# rso.net
KiCad netlist of a schematic drawn in EAGLE
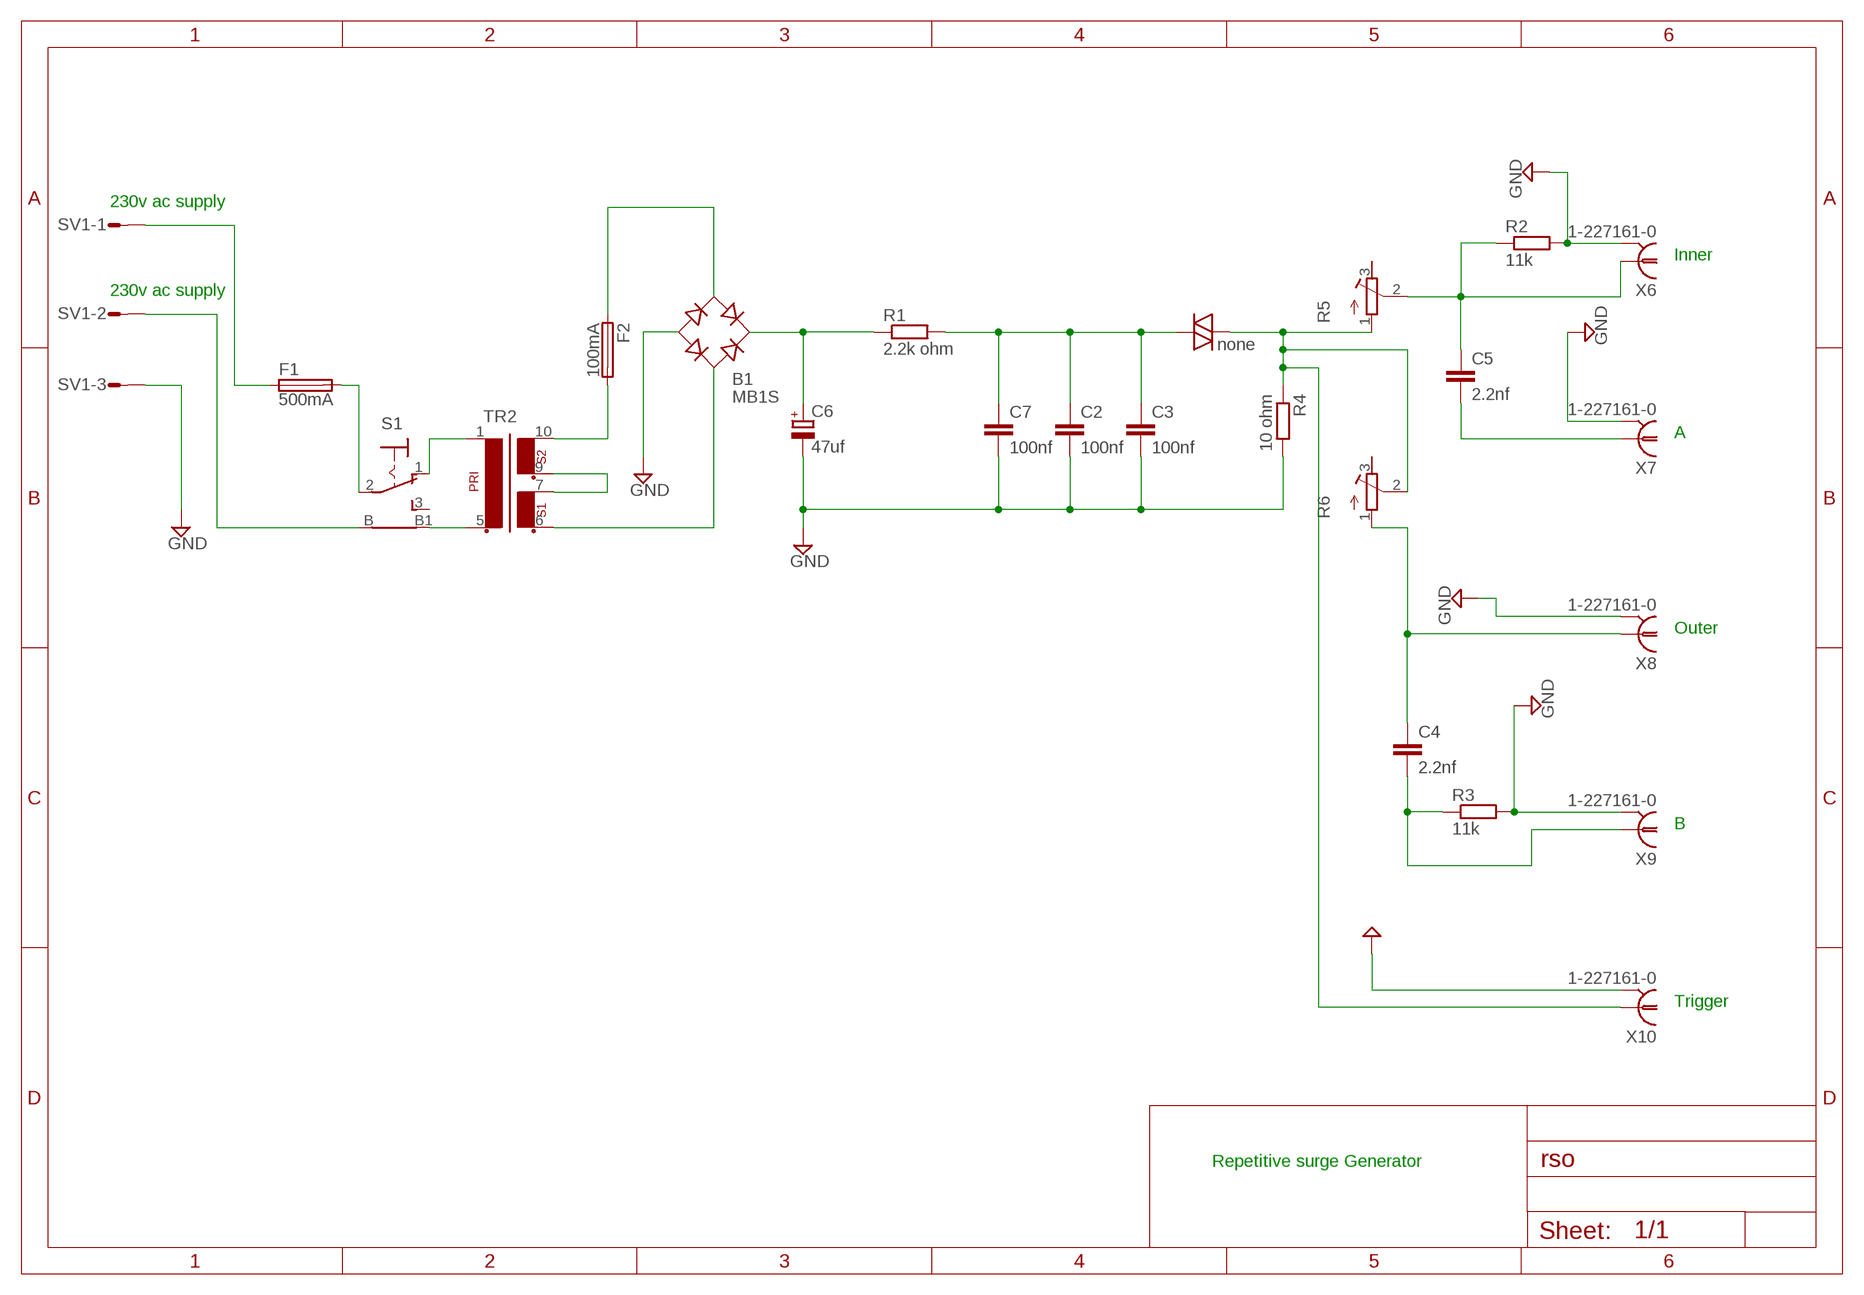
[diagram p0: schematic, sheet 1]

(export (version "E")
  (design (tool "Eeschema 10.0.6"))
  (components
    (comp (ref "B1")
      (value "MB1S")
      (footprint "eagle-import:SOIC-4")
      (fields (field (name "MF") "MULTICOMP"))
      (libsource (lib "eagle-import") (part "MBS1"))
    )
    (comp (ref "C2")
      (value "100nf")
      (footprint "eagle-import:C0805")
      (fields (field (name "MF") "AVX") (field (name "MPN") "08055C104KAZ2A"))
      (libsource (lib "eagle-import") (part "C-EUC0805"))
    )
    (comp (ref "C3")
      (value "100nf")
      (footprint "eagle-import:C0805")
      (fields (field (name "MF") "AVX") (field (name "MPN") "08055C104KAZ2A"))
      (libsource (lib "eagle-import") (part "C-EUC0805"))
    )
    (comp (ref "C4")
      (value "2.2nf")
      (footprint "eagle-import:C0805")
      (fields (field (name "MF") "AVX") (field (name "MPN") "04025C222JAT2A"))
      (libsource (lib "eagle-import") (part "C-EUC0805"))
    )
    (comp (ref "C5")
      (value "2.2nf")
      (footprint "eagle-import:C0805")
      (fields (field (name "MF") "AVX") (field (name "MPN") "04025C222JAT2A"))
      (libsource (lib "eagle-import") (part "C-EUC0805"))
    )
    (comp (ref "C6")
      (value "47uf")
      (footprint "eagle-import:140CLH-1010")
      (fields (field (name "MF") "PANASONIC") (field (name "MPN") "EEEFK1K470P"))
      (libsource (lib "eagle-import") (part "CPOL-EU140CLH-1010"))
    )
    (comp (ref "C7")
      (value "100nf")
      (footprint "eagle-import:C0805")
      (fields (field (name "MF") "AVX") (field (name "MPN") "08055C104KAZ2A"))
      (libsource (lib "eagle-import") (part "C-EUC0805"))
    )
    (comp (ref "D1")
      (value "none")
      (footprint "eagle-import:DO35-10")
      (fields (field (name "MF") "NTE ELECTRONICS") (field (name "MPN") "NTE6408"))
      (libsource (lib "eagle-import") (part "DIAC-DO35-10"))
    )
    (comp (ref "F1")
      (value "500mA")
      (footprint "eagle-import:SH22,5A")
      (fields
        (field (name "MPN") "0031.7701.11")
        (field (name "MF") "ARCOLECTRIC")
        (field (name "MPN_1") "C0345RAAAA")
        (field (name "OC_FARNELL") "149862")
      )
      (libsource (lib "eagle-import") (part "SH22,5A"))
    )
    (comp (ref "F2")
      (value "100mA")
      (footprint "eagle-import:SH22,5A")
      (fields
        (field (name "MPN") "0031.7701.11")
        (field (name "MF") "ARCOLECTRIC")
        (field (name "MPN_1") "C0345RAAAA")
        (field (name "OC_FARNELL") "149862")
      )
      (libsource (lib "eagle-import") (part "SH22,5A"))
    )
    (comp (ref "R1")
      (value "2.2k ohm")
      (footprint "eagle-import:R2512W")
      (fields (field (name "MF") "VISHAY") (field (name "MPN") "CRCW08052K20FKEA"))
      (libsource (lib "eagle-import") (part "R-EU_R2512W"))
    )
    (comp (ref "R2")
      (value "11k")
      (footprint "eagle-import:M0805")
      (fields (field (name "MF") "MULTICOMP") (field (name "MPN") "MCMR08X1102FTL"))
      (libsource (lib "eagle-import") (part "R-EU_M0805"))
    )
    (comp (ref "R3")
      (value "11k")
      (footprint "eagle-import:M0805")
      (fields (field (name "MF") "MULTICOMP") (field (name "MPN") "MCMR08X1102FTL"))
      (libsource (lib "eagle-import") (part "R-EU_M0805"))
    )
    (comp (ref "R4")
      (value "10 ohm")
      (footprint "eagle-import:M0805")
      (fields (field (name "MF") "BOURNS") (field (name "MPN") "CRT1206-BY-10R0ELF"))
      (libsource (lib "eagle-import") (part "R-EU_M0805"))
    )
    (comp (ref "R5")
      (value "R-TRIMM3339P")
      (footprint "eagle-import:RTRIM3339P")
      (fields (field (name "MF") "VISHAY") (field (name "MPN") "534B1101JL"))
      (libsource (lib "eagle-import") (part "R-TRIMM3339P"))
    )
    (comp (ref "R6")
      (value "R-TRIMM3339P")
      (footprint "eagle-import:RTRIM3339P")
      (fields (field (name "MF") "VISHAY") (field (name "MPN") "534B1101JL"))
      (libsource (lib "eagle-import") (part "R-TRIMM3339P"))
    )
    (comp (ref "S1")
      (value "LPV-1")
      (footprint "eagle-import:LPV-1")
      (fields (field (name "MF") "QUALTEK ELECTRONICS") (field (name "MPN") "761-18/003"))
      (libsource (lib "eagle-import") (part "LPV-1"))
    )
    (comp (ref "SV1")
      (value "L03P")
      (footprint "eagle-import:L03P")
      (fields
        (field (name "MF") "JST (JAPAN SOLDERLESS TERMINALS)")
        (field (name "MPN") "B03B-XASK-1(LF)(SN)")
        (field (name "OC_FARNELL") "9492070")
      )
      (libsource (lib "eagle-import") (part "L03P"))
    )
    (comp (ref "TR2")
      (value "EI38-2")
      (footprint "eagle-import:EI38-2")
      (fields (field (name "MF") "MYRRA") (field (name "MPN") "44203"))
      (libsource (lib "eagle-import") (part "EI38-2"))
    )
    (comp (ref "X6")
      (value "1-227161-0")
      (footprint "eagle-import:AMP_227161")
      (fields
        (field (name "MF") "TYCO ELECTRONICS")
        (field (name "MPN") "1-227161")
        (field (name "MF_1") "GREENPAR - TE CONNECTIVITY")
        (field (name "MPN_1") "1-1337542-0")
        (field (name "OC_FARNELL") "1020954")
      )
      (libsource (lib "eagle-import") (part "?2271611--0"))
    )
    (comp (ref "X7")
      (value "1-227161-0")
      (footprint "eagle-import:AMP_227161")
      (fields
        (field (name "MF") "TYCO ELECTRONICS")
        (field (name "MPN") "1-227161")
        (field (name "MF_1") "GREENPAR - TE CONNECTIVITY")
        (field (name "MPN_1") "1-1337542-0")
        (field (name "OC_FARNELL") "1020954")
      )
      (libsource (lib "eagle-import") (part "?2271611--0"))
    )
    (comp (ref "X8")
      (value "1-227161-0")
      (footprint "eagle-import:AMP_227161")
      (fields
        (field (name "MF") "TYCO ELECTRONICS")
        (field (name "MPN") "1-227161")
        (field (name "MF_1") "GREENPAR - TE CONNECTIVITY")
        (field (name "MPN_1") "1-1337542-0")
        (field (name "OC_FARNELL") "1020954")
      )
      (libsource (lib "eagle-import") (part "?2271611--0"))
    )
    (comp (ref "X9")
      (value "1-227161-0")
      (footprint "eagle-import:AMP_227161")
      (fields
        (field (name "MF") "TYCO ELECTRONICS")
        (field (name "MPN") "1-227161")
        (field (name "MF_1") "GREENPAR - TE CONNECTIVITY")
        (field (name "MPN_1") "1-1337542-0")
        (field (name "OC_FARNELL") "1020954")
      )
      (libsource (lib "eagle-import") (part "?2271611--0"))
    )
    (comp (ref "X10")
      (value "1-227161-0")
      (footprint "eagle-import:AMP_227161")
      (fields
        (field (name "MF") "TYCO ELECTRONICS")
        (field (name "MPN") "1-227161")
        (field (name "MF_1") "GREENPAR - TE CONNECTIVITY")
        (field (name "MPN_1") "1-1337542-0")
        (field (name "OC_FARNELL") "1020954")
      )
      (libsource (lib "eagle-import") (part "?2271611--0"))
    )
  )
  (nets
    (net (code "1") (name "GND") (class "Default")
      (node (ref "B1") (pin "-") (pinfunction "-_-") (pintype "passive"))
      (node (ref "C2") (pin "2") (pinfunction "2_2") (pintype "passive"))
      (node (ref "C3") (pin "2") (pinfunction "2_2") (pintype "passive"))
      (node (ref "C6") (pin "-") (pinfunction "-_-") (pintype "passive"))
      (node (ref "C7") (pin "2") (pinfunction "2_2") (pintype "passive"))
      (node (ref "R2") (pin "2") (pinfunction "2_2") (pintype "passive"))
      (node (ref "R3") (pin "2") (pinfunction "2_2") (pintype "passive"))
      (node (ref "R4") (pin "2") (pinfunction "2_2") (pintype "passive"))
      (node (ref "SV1") (pin "3") (pinfunction "S_3") (pintype "passive"))
      (node (ref "X10") (pin "2") (pinfunction "2_2") (pintype "passive"))
      (node (ref "X6") (pin "2") (pinfunction "2_2") (pintype "passive"))
      (node (ref "X7") (pin "2") (pinfunction "2_2") (pintype "passive"))
      (node (ref "X8") (pin "2") (pinfunction "2_2") (pintype "passive"))
      (node (ref "X9") (pin "2") (pinfunction "2_2") (pintype "passive"))
    )
    (net (code "2") (name "Net-(B1-AC1)") (class "Default")
      (node (ref "B1") (pin "~1") (pinfunction "AC1_~1") (pintype "passive"))
      (node (ref "F2") (pin "1") (pinfunction "1_1") (pintype "passive"))
    )
    (net (code "3") (name "Net-(B1-AC2)") (class "Default")
      (node (ref "B1") (pin "~2") (pinfunction "AC2_~2") (pintype "passive"))
      (node (ref "TR2") (pin "6") (pinfunction "3_6") (pintype "passive"))
    )
    (net (code "4") (name "Net-(B1-Pad+)") (class "Default")
      (node (ref "B1") (pin "+") (pinfunction "+_+") (pintype "passive"))
      (node (ref "C6") (pin "+") (pinfunction "+_+") (pintype "passive"))
      (node (ref "R1") (pin "1") (pinfunction "1_1") (pintype "passive"))
    )
    (net (code "5") (name "Net-(C4-Pad2)") (class "Default")
      (node (ref "C4") (pin "2") (pinfunction "2_2") (pintype "passive"))
      (node (ref "R3") (pin "1") (pinfunction "1_1") (pintype "passive"))
      (node (ref "X9") (pin "1") (pinfunction "1_1") (pintype "passive"))
    )
    (net (code "6") (name "Net-(C5-Pad2)") (class "Default")
      (node (ref "C5") (pin "2") (pinfunction "2_2") (pintype "passive"))
      (node (ref "X7") (pin "1") (pinfunction "1_1") (pintype "passive"))
    )
    (net (code "7") (name "Net-(D1-1)") (class "Default")
      (node (ref "C2") (pin "1") (pinfunction "1_1") (pintype "passive"))
      (node (ref "C3") (pin "1") (pinfunction "1_1") (pintype "passive"))
      (node (ref "C7") (pin "1") (pinfunction "1_1") (pintype "passive"))
      (node (ref "D1") (pin "A") (pinfunction "1_A") (pintype "passive"))
      (node (ref "R1") (pin "2") (pinfunction "2_2") (pintype "passive"))
    )
    (net (code "8") (name "Net-(D1-2)") (class "Default")
      (node (ref "D1") (pin "C") (pinfunction "2_C") (pintype "passive"))
      (node (ref "R4") (pin "1") (pinfunction "1_1") (pintype "passive"))
      (node (ref "R5") (pin "1") (pinfunction "A_1") (pintype "passive"))
      (node (ref "R6") (pin "2") (pinfunction "S_2") (pintype "passive"))
      (node (ref "X10") (pin "1") (pinfunction "1_1") (pintype "passive"))
    )
    (net (code "9") (name "Net-(R5-S)") (class "Default")
      (node (ref "C5") (pin "1") (pinfunction "1_1") (pintype "passive"))
      (node (ref "R2") (pin "1") (pinfunction "1_1") (pintype "passive"))
      (node (ref "R5") (pin "2") (pinfunction "S_2") (pintype "passive"))
      (node (ref "X6") (pin "1") (pinfunction "1_1") (pintype "passive"))
    )
    (net (code "10") (name "Net-(R6-A)") (class "Default")
      (node (ref "C4") (pin "1") (pinfunction "1_1") (pintype "passive"))
      (node (ref "R6") (pin "1") (pinfunction "A_1") (pintype "passive"))
      (node (ref "X8") (pin "1") (pinfunction "1_1") (pintype "passive"))
    )
    (net (code "11") (name "Net-(S1-O)") (class "Default")
      (node (ref "S1") (pin "1") (pinfunction "O_1") (pintype "passive"))
      (node (ref "TR2") (pin "1") (pinfunction "1_1") (pintype "passive"))
    )
    (net (code "12") (name "Net-(S1-P)") (class "Default")
      (node (ref "F1") (pin "2") (pinfunction "2_2") (pintype "passive"))
      (node (ref "S1") (pin "2") (pinfunction "P_2") (pintype "passive"))
    )
    (net (code "13") (name "Net-(SV1A-S)") (class "Default")
      (node (ref "F1") (pin "1") (pinfunction "1_1") (pintype "passive"))
      (node (ref "SV1") (pin "1") (pinfunction "S_1") (pintype "passive"))
    )
    (net (code "14") (name "Net-(SV1B-S)") (class "Default")
      (node (ref "S1") (pin "B") (pinfunction "B_B") (pintype "passive"))
      (node (ref "SV1") (pin "2") (pinfunction "S_2") (pintype "passive"))
    )
    (net (code "15") (name "Net-(TR2-2)") (class "Default")
      (node (ref "S1") (pin "B1") (pinfunction "B1_B1") (pintype "passive"))
      (node (ref "TR2") (pin "5") (pinfunction "2_5") (pintype "passive"))
    )
    (net (code "16") (name "Net-(TR2-4)") (class "Default")
      (node (ref "TR2") (pin "7") (pinfunction "4_7") (pintype "passive"))
      (node (ref "TR2") (pin "9") (pinfunction "5_9") (pintype "passive"))
    )
    (net (code "17") (name "Net-(TR2-6)") (class "Default")
      (node (ref "F2") (pin "2") (pinfunction "2_2") (pintype "passive"))
      (node (ref "TR2") (pin "10") (pinfunction "6_10") (pintype "passive"))
    )
    (net (code "18") (name "unconnected-(R5-E-Pad3)") (class "Default")
      (node (ref "R5") (pin "3") (pinfunction "E_3") (pintype "passive"))
    )
    (net (code "19") (name "unconnected-(R6-E-Pad3)") (class "Default")
      (node (ref "R6") (pin "3") (pinfunction "E_3") (pintype "passive"))
    )
    (net (code "20") (name "unconnected-(S1-S-Pad3)") (class "Default")
      (node (ref "S1") (pin "3") (pinfunction "S_3") (pintype "passive"))
    )
  )
)
